# Topcheat.net
KiCad netlist of a schematic drawn in Altium Designer
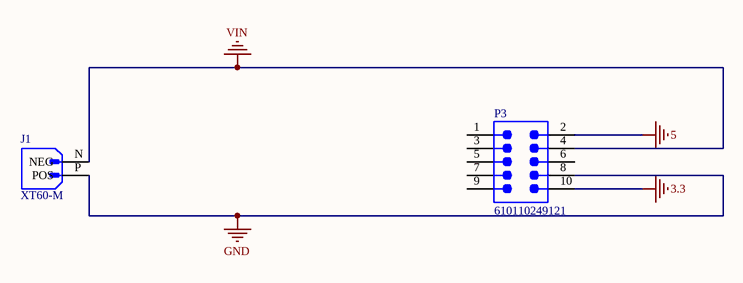
[diagram p0: Topcheat.SchDoc]

(export (version "E")
  (design (tool "Eeschema 10.0.6"))
  (components
    (comp (ref "J1")
      (value "XT60-M")
      (footprint "AMASS_XT60-M")
      (description "Plug; DC supply; XT60; male; PIN: 2; for cable; soldered; 30A; 500V")
      (fields (field (name "MF") "AMASS"))
      (libsource (lib "Linköpings Universitet") (part "XT60-M"))
    )
    (comp (ref "P3")
      (value "610110249121")
      (footprint "610110249121")
      (description "Board Connector, 10 Contact(s), 2 Row(s), Male, Right Angle, Surface Mount Terminal")
      (libsource (lib "Linköpings Universitet") (part "Header_Male_2R_10P"))
    )
  )
  (nets
    (net (code "1") (name "3.3") (class "Default")
      (node (ref "P3") (pin "10") (pinfunction "10_10") (pintype "passive"))
    )
    (net (code "2") (name "5") (class "Default")
      (node (ref "P3") (pin "2") (pinfunction "2_2") (pintype "passive"))
    )
    (net (code "3") (name "GND") (class "Default")
      (node (ref "J1") (pin "P") (pinfunction "POS_P") (pintype "passive"))
      (node (ref "P3") (pin "8") (pinfunction "8_8") (pintype "passive"))
    )
    (net (code "4") (name "VIN") (class "Default")
      (node (ref "J1") (pin "N") (pinfunction "NEG_N") (pintype "passive"))
      (node (ref "P3") (pin "4") (pinfunction "4_4") (pintype "passive"))
    )
    (net (code "5") (name "unconnected-(P3-Pad1)") (class "Default")
      (node (ref "P3") (pin "1") (pinfunction "1_1") (pintype "passive"))
    )
    (net (code "6") (name "unconnected-(P3-Pad3)") (class "Default")
      (node (ref "P3") (pin "3") (pinfunction "3_3") (pintype "passive"))
    )
    (net (code "7") (name "unconnected-(P3-Pad5)") (class "Default")
      (node (ref "P3") (pin "5") (pinfunction "5_5") (pintype "passive"))
    )
    (net (code "8") (name "unconnected-(P3-Pad6)") (class "Default")
      (node (ref "P3") (pin "6") (pinfunction "6_6") (pintype "passive"))
    )
    (net (code "9") (name "unconnected-(P3-Pad7)") (class "Default")
      (node (ref "P3") (pin "7") (pinfunction "7_7") (pintype "passive"))
    )
    (net (code "10") (name "unconnected-(P3-Pad9)") (class "Default")
      (node (ref "P3") (pin "9") (pinfunction "9_9") (pintype "passive"))
    )
  )
)
